# untitled.net
KiCad netlist of a schematic drawn in EAGLE
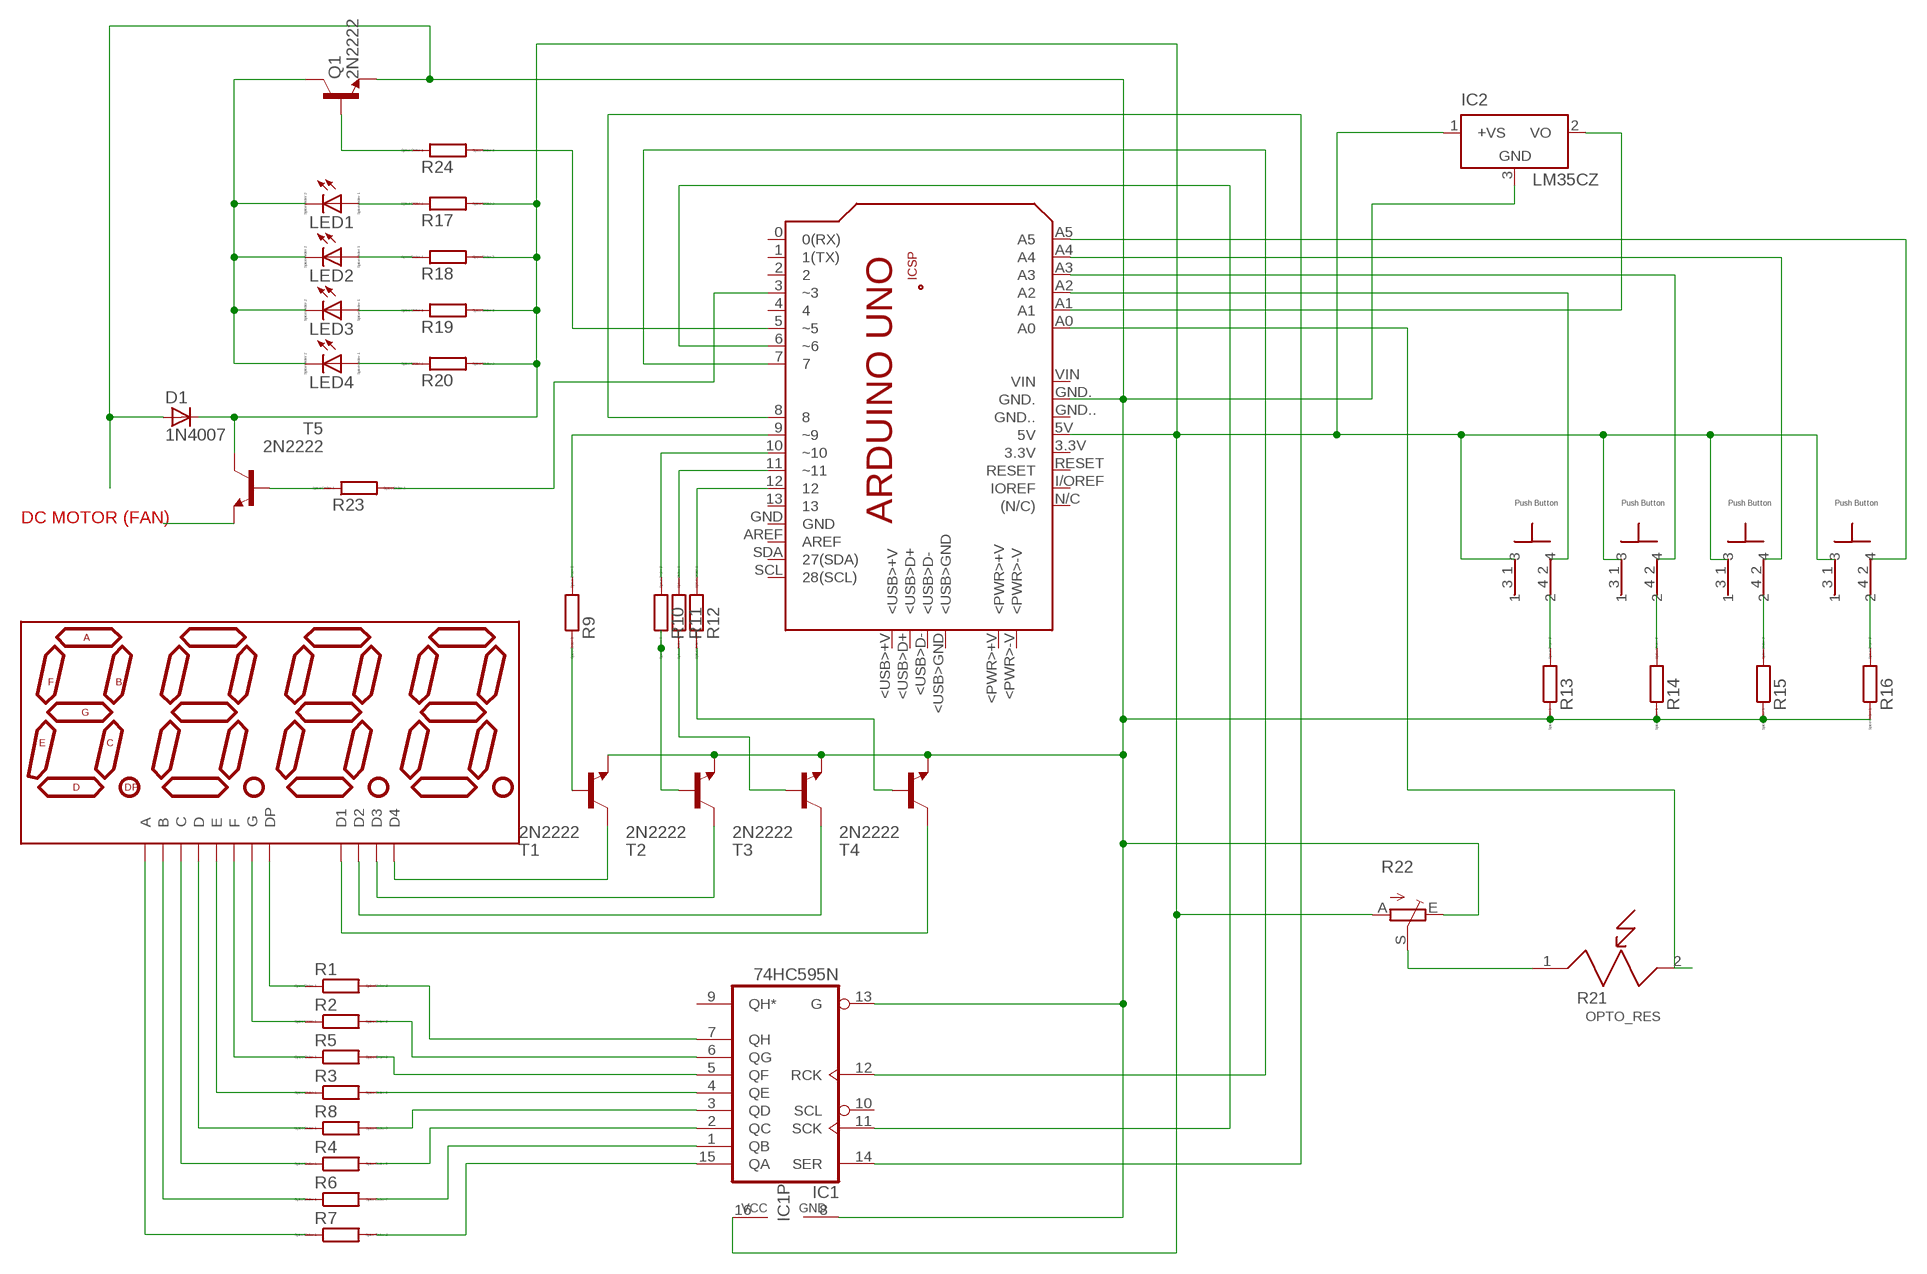
[diagram p0: schematic, sheet 1]

(export (version "E")
  (design (tool "Eeschema 10.0.6"))
  (components
    (comp (ref "D1")
      (value "1N4007")
      (footprint "eagle-import:SMA")
      (libsource (lib "eagle-import") (part "1N4007"))
    )
    (comp (ref "DISP1")
      (value "7-SEGMENT-4DIGIT-COUNTERPTH")
      (footprint "eagle-import:7-SEGMENT-4DIGIT-COUNTER")
      (libsource (lib "eagle-import") (part "7-SEGMENT-4DIGIT-COUNTERPTH"))
    )
    (comp (ref "IC1")
      (value "74HC595N")
      (footprint "eagle-import:DIL16")
      (libsource (lib "eagle-import") (part "74595NHC"))
    )
    (comp (ref "IC2")
      (value "LM35CZ")
      (footprint "eagle-import:TO92")
      (libsource (lib "eagle-import") (part "LM35CZ"))
    )
    (comp (ref "LED1")
      (value "LED_ELD260")
      (footprint "eagle-import:LED_LD260")
      (libsource (lib "eagle-import") (part "LED_ELD260"))
    )
    (comp (ref "LED2")
      (value "LED_ELD260")
      (footprint "eagle-import:LED_LD260")
      (libsource (lib "eagle-import") (part "LED_ELD260"))
    )
    (comp (ref "LED3")
      (value "LED_ELD260")
      (footprint "eagle-import:LED_LD260")
      (libsource (lib "eagle-import") (part "LED_ELD260"))
    )
    (comp (ref "LED4")
      (value "LED_ELD260")
      (footprint "eagle-import:LED_LD260")
      (libsource (lib "eagle-import") (part "LED_ELD260"))
    )
    (comp (ref "PCB1")
      (value "ARDUINO_UNO")
      (footprint "eagle-import:ARDUINO_UNO")
      (libsource (lib "eagle-import") (part "ARDUINO_UNO"))
    )
    (comp (ref "Q1")
      (value "2N2222")
      (footprint "eagle-import:TO18")
      (libsource (lib "eagle-import") (part "2N2222"))
    )
    (comp (ref "R1")
      (value "R0207/10")
      (footprint "eagle-import:0207_10")
      (libsource (lib "eagle-import") (part "R0207/10"))
    )
    (comp (ref "R2")
      (value "R0207/10")
      (footprint "eagle-import:0207_10")
      (libsource (lib "eagle-import") (part "R0207/10"))
    )
    (comp (ref "R3")
      (value "R0207/10")
      (footprint "eagle-import:0207_10")
      (libsource (lib "eagle-import") (part "R0207/10"))
    )
    (comp (ref "R4")
      (value "R0207/10")
      (footprint "eagle-import:0207_10")
      (libsource (lib "eagle-import") (part "R0207/10"))
    )
    (comp (ref "R5")
      (value "R0207/10")
      (footprint "eagle-import:0207_10")
      (libsource (lib "eagle-import") (part "R0207/10"))
    )
    (comp (ref "R6")
      (value "R0207/10")
      (footprint "eagle-import:0207_10")
      (libsource (lib "eagle-import") (part "R0207/10"))
    )
    (comp (ref "R7")
      (value "R0207/10")
      (footprint "eagle-import:0207_10")
      (libsource (lib "eagle-import") (part "R0207/10"))
    )
    (comp (ref "R8")
      (value "R0207/10")
      (footprint "eagle-import:0207_10")
      (libsource (lib "eagle-import") (part "R0207/10"))
    )
    (comp (ref "R9")
      (value "R0207/10")
      (footprint "eagle-import:0207_10")
      (libsource (lib "eagle-import") (part "R0207/10"))
    )
    (comp (ref "R10")
      (value "R0207/10")
      (footprint "eagle-import:0207_10")
      (libsource (lib "eagle-import") (part "R0207/10"))
    )
    (comp (ref "R11")
      (value "R0207/10")
      (footprint "eagle-import:0207_10")
      (libsource (lib "eagle-import") (part "R0207/10"))
    )
    (comp (ref "R12")
      (value "R0207/10")
      (footprint "eagle-import:0207_10")
      (libsource (lib "eagle-import") (part "R0207/10"))
    )
    (comp (ref "R13")
      (value "R0207/10")
      (footprint "eagle-import:0207_10")
      (libsource (lib "eagle-import") (part "R0207/10"))
    )
    (comp (ref "R14")
      (value "R0207/10")
      (footprint "eagle-import:0207_10")
      (libsource (lib "eagle-import") (part "R0207/10"))
    )
    (comp (ref "R15")
      (value "R0207/10")
      (footprint "eagle-import:0207_10")
      (libsource (lib "eagle-import") (part "R0207/10"))
    )
    (comp (ref "R16")
      (value "R0207/10")
      (footprint "eagle-import:0207_10")
      (libsource (lib "eagle-import") (part "R0207/10"))
    )
    (comp (ref "R17")
      (value "R0207/10")
      (footprint "eagle-import:0207_10")
      (libsource (lib "eagle-import") (part "R0207/10"))
    )
    (comp (ref "R18")
      (value "R0207/10")
      (footprint "eagle-import:0207_10")
      (libsource (lib "eagle-import") (part "R0207/10"))
    )
    (comp (ref "R19")
      (value "R0207/10")
      (footprint "eagle-import:0207_10")
      (libsource (lib "eagle-import") (part "R0207/10"))
    )
    (comp (ref "R20")
      (value "R0207/10")
      (footprint "eagle-import:0207_10")
      (libsource (lib "eagle-import") (part "R0207/10"))
    )
    (comp (ref "R21")
      (value "OPTO_RES")
      (footprint "eagle-import:OPTO_RES")
      (libsource (lib "eagle-import") (part "OPTO_RES"))
    )
    (comp (ref "R22")
      (value "TRIM_EU-LI10")
      (footprint "eagle-import:LI10")
      (libsource (lib "eagle-import") (part "TRIM_EU-LI10"))
    )
    (comp (ref "R23")
      (value "R0207/10")
      (footprint "eagle-import:0207_10")
      (libsource (lib "eagle-import") (part "R0207/10"))
    )
    (comp (ref "R24")
      (value "R0207/10")
      (footprint "eagle-import:0207_10")
      (libsource (lib "eagle-import") (part "R0207/10"))
    )
    (comp (ref "T1")
      (value "2N2222")
      (footprint "eagle-import:TO18")
      (libsource (lib "eagle-import") (part "transistor_2N2222"))
    )
    (comp (ref "T2")
      (value "2N2222")
      (footprint "eagle-import:TO18")
      (libsource (lib "eagle-import") (part "transistor_2N2222"))
    )
    (comp (ref "T3")
      (value "2N2222")
      (footprint "eagle-import:TO18")
      (libsource (lib "eagle-import") (part "transistor_2N2222"))
    )
    (comp (ref "T4")
      (value "2N2222")
      (footprint "eagle-import:TO18")
      (libsource (lib "eagle-import") (part "transistor_2N2222"))
    )
    (comp (ref "T5")
      (value "2N2222")
      (footprint "eagle-import:TO18")
      (libsource (lib "eagle-import") (part "transistor_2N2222"))
    )
    (comp (ref "U$1")
      (value "PUSHBTN")
      (footprint "eagle-import:PUSHBTN")
      (libsource (lib "eagle-import") (part "PUSHBTN"))
    )
    (comp (ref "U$2")
      (value "PUSHBTN")
      (footprint "eagle-import:PUSHBTN")
      (libsource (lib "eagle-import") (part "PUSHBTN"))
    )
    (comp (ref "U$3")
      (value "PUSHBTN")
      (footprint "eagle-import:PUSHBTN")
      (libsource (lib "eagle-import") (part "PUSHBTN"))
    )
    (comp (ref "U$4")
      (value "PUSHBTN")
      (footprint "eagle-import:PUSHBTN")
      (libsource (lib "eagle-import") (part "PUSHBTN"))
    )
  )
  (nets
    (net (code "1") (name "Net-(D1-C)") (class "Default")
      (node (ref "D1") (pin "K") (pinfunction "C_K") (pintype "passive"))
      (node (ref "IC1") (pin "16") (pinfunction "VCC_16") (pintype "power_in"))
      (node (ref "IC2") (pin "1") (pinfunction "+VS_1") (pintype "input"))
      (node (ref "PCB1") (pin "5V") (pinfunction "5V_5V") (pintype "bidirectional"))
      (node (ref "R17") (pin "2") (pinfunction "2_2") (pintype "passive"))
      (node (ref "R18") (pin "2") (pinfunction "2_2") (pintype "passive"))
      (node (ref "R19") (pin "2") (pinfunction "2_2") (pintype "passive"))
      (node (ref "R20") (pin "2") (pinfunction "2_2") (pintype "passive"))
      (node (ref "R22") (pin "A") (pinfunction "A_A") (pintype "passive"))
      (node (ref "T5") (pin "3") (pinfunction "C_3") (pintype "passive"))
      (node (ref "U$1") (pin "1") (pinfunction "1_1") (pintype "bidirectional"))
      (node (ref "U$2") (pin "1") (pinfunction "1_1") (pintype "bidirectional"))
      (node (ref "U$3") (pin "1") (pinfunction "1_1") (pintype "bidirectional"))
      (node (ref "U$4") (pin "1") (pinfunction "1_1") (pintype "bidirectional"))
    )
    (net (code "2") (name "Net-(DISP1-A)") (class "Default")
      (node (ref "DISP1") (pin "11") (pinfunction "A_11") (pintype "bidirectional"))
      (node (ref "R7") (pin "1") (pinfunction "1_1") (pintype "passive"))
    )
    (net (code "3") (name "Net-(DISP1-B)") (class "Default")
      (node (ref "DISP1") (pin "7") (pinfunction "B_7") (pintype "bidirectional"))
      (node (ref "R6") (pin "1") (pinfunction "1_1") (pintype "passive"))
    )
    (net (code "4") (name "Net-(DISP1-C)") (class "Default")
      (node (ref "DISP1") (pin "4") (pinfunction "C_4") (pintype "bidirectional"))
      (node (ref "R4") (pin "1") (pinfunction "1_1") (pintype "passive"))
    )
    (net (code "5") (name "Net-(DISP1-D)") (class "Default")
      (node (ref "DISP1") (pin "2") (pinfunction "D_2") (pintype "bidirectional"))
      (node (ref "R8") (pin "1") (pinfunction "1_1") (pintype "passive"))
    )
    (net (code "6") (name "Net-(DISP1-D1)") (class "Default")
      (node (ref "DISP1") (pin "12") (pinfunction "D1_12") (pintype "bidirectional"))
      (node (ref "T4") (pin "3") (pinfunction "C_3") (pintype "passive"))
    )
    (net (code "7") (name "Net-(DISP1-D2)") (class "Default")
      (node (ref "DISP1") (pin "9") (pinfunction "D2_9") (pintype "bidirectional"))
      (node (ref "T3") (pin "3") (pinfunction "C_3") (pintype "passive"))
    )
    (net (code "8") (name "Net-(DISP1-D3)") (class "Default")
      (node (ref "DISP1") (pin "8") (pinfunction "D3_8") (pintype "bidirectional"))
      (node (ref "T2") (pin "3") (pinfunction "C_3") (pintype "passive"))
    )
    (net (code "9") (name "Net-(DISP1-D4)") (class "Default")
      (node (ref "DISP1") (pin "6") (pinfunction "D4_6") (pintype "bidirectional"))
      (node (ref "T1") (pin "3") (pinfunction "C_3") (pintype "passive"))
    )
    (net (code "10") (name "Net-(DISP1-DP)") (class "Default")
      (node (ref "DISP1") (pin "3") (pinfunction "DP_3") (pintype "bidirectional"))
      (node (ref "R1") (pin "1") (pinfunction "1_1") (pintype "passive"))
    )
    (net (code "11") (name "Net-(DISP1-E)") (class "Default")
      (node (ref "DISP1") (pin "1") (pinfunction "E_1") (pintype "bidirectional"))
      (node (ref "R3") (pin "1") (pinfunction "1_1") (pintype "passive"))
    )
    (net (code "12") (name "Net-(DISP1-F)") (class "Default")
      (node (ref "DISP1") (pin "10") (pinfunction "F_10") (pintype "bidirectional"))
      (node (ref "R5") (pin "1") (pinfunction "1_1") (pintype "passive"))
    )
    (net (code "13") (name "Net-(DISP1-G)") (class "Default")
      (node (ref "DISP1") (pin "5") (pinfunction "G_5") (pintype "bidirectional"))
      (node (ref "R2") (pin "1") (pinfunction "1_1") (pintype "passive"))
    )
    (net (code "14") (name "Net-(IC1A-G)") (class "Default")
      (node (ref "D1") (pin "A") (pinfunction "A_A") (pintype "passive"))
      (node (ref "IC1") (pin "13") (pinfunction "G_13") (pintype "input"))
      (node (ref "IC1") (pin "8") (pinfunction "GND_8") (pintype "power_in"))
      (node (ref "IC2") (pin "3") (pinfunction "GND_3") (pintype "power_in"))
      (node (ref "PCB1") (pin "GND.") (pinfunction "GND._GND.") (pintype "bidirectional"))
      (node (ref "Q1") (pin "1") (pinfunction "E_1") (pintype "passive"))
      (node (ref "R13") (pin "1") (pinfunction "1_1") (pintype "passive"))
      (node (ref "R14") (pin "1") (pinfunction "1_1") (pintype "passive"))
      (node (ref "R15") (pin "1") (pinfunction "1_1") (pintype "passive"))
      (node (ref "R16") (pin "1") (pinfunction "1_1") (pintype "passive"))
      (node (ref "R22") (pin "E") (pinfunction "E_E") (pintype "passive"))
      (node (ref "T1") (pin "1") (pinfunction "E_1") (pintype "passive"))
      (node (ref "T2") (pin "1") (pinfunction "E_1") (pintype "passive"))
      (node (ref "T3") (pin "1") (pinfunction "E_1") (pintype "passive"))
      (node (ref "T4") (pin "1") (pinfunction "E_1") (pintype "passive"))
    )
    (net (code "15") (name "Net-(IC1A-QA)") (class "Default")
      (node (ref "IC1") (pin "15") (pinfunction "QA_15") (pintype "tri_state"))
      (node (ref "R7") (pin "2") (pinfunction "2_2") (pintype "passive"))
    )
    (net (code "16") (name "Net-(IC1A-QB)") (class "Default")
      (node (ref "IC1") (pin "1") (pinfunction "QB_1") (pintype "tri_state"))
      (node (ref "R6") (pin "2") (pinfunction "2_2") (pintype "passive"))
    )
    (net (code "17") (name "Net-(IC1A-QC)") (class "Default")
      (node (ref "IC1") (pin "2") (pinfunction "QC_2") (pintype "tri_state"))
      (node (ref "R4") (pin "2") (pinfunction "2_2") (pintype "passive"))
    )
    (net (code "18") (name "Net-(IC1A-QD)") (class "Default")
      (node (ref "IC1") (pin "3") (pinfunction "QD_3") (pintype "tri_state"))
      (node (ref "R8") (pin "2") (pinfunction "2_2") (pintype "passive"))
    )
    (net (code "19") (name "Net-(IC1A-QE)") (class "Default")
      (node (ref "IC1") (pin "4") (pinfunction "QE_4") (pintype "tri_state"))
      (node (ref "R3") (pin "2") (pinfunction "2_2") (pintype "passive"))
    )
    (net (code "20") (name "Net-(IC1A-QF)") (class "Default")
      (node (ref "IC1") (pin "5") (pinfunction "QF_5") (pintype "tri_state"))
      (node (ref "R5") (pin "2") (pinfunction "2_2") (pintype "passive"))
    )
    (net (code "21") (name "Net-(IC1A-QG)") (class "Default")
      (node (ref "IC1") (pin "6") (pinfunction "QG_6") (pintype "tri_state"))
      (node (ref "R2") (pin "2") (pinfunction "2_2") (pintype "passive"))
    )
    (net (code "22") (name "Net-(IC1A-QH)") (class "Default")
      (node (ref "IC1") (pin "7") (pinfunction "QH_7") (pintype "tri_state"))
      (node (ref "R1") (pin "2") (pinfunction "2_2") (pintype "passive"))
    )
    (net (code "23") (name "Net-(IC1A-RCK)") (class "Default")
      (node (ref "IC1") (pin "12") (pinfunction "RCK_12") (pintype "input"))
      (node (ref "PCB1") (pin "7") (pinfunction "7_7") (pintype "bidirectional"))
    )
    (net (code "24") (name "Net-(IC1A-SCK)") (class "Default")
      (node (ref "IC1") (pin "11") (pinfunction "SCK_11") (pintype "input"))
      (node (ref "PCB1") (pin "6") (pinfunction "~{6}_6") (pintype "bidirectional"))
    )
    (net (code "25") (name "Net-(IC1A-SER)") (class "Default")
      (node (ref "IC1") (pin "14") (pinfunction "SER_14") (pintype "input"))
      (node (ref "PCB1") (pin "8") (pinfunction "8_8") (pintype "bidirectional"))
    )
    (net (code "26") (name "Net-(IC2-VO)") (class "Default")
      (node (ref "IC2") (pin "2") (pinfunction "VO_2") (pintype "input"))
      (node (ref "PCB1") (pin "A1") (pinfunction "A1_A1") (pintype "bidirectional"))
    )
    (net (code "27") (name "Net-(LED1-C)") (class "Default")
      (node (ref "LED1") (pin "K") (pinfunction "C_K") (pintype "passive"))
      (node (ref "LED2") (pin "K") (pinfunction "C_K") (pintype "passive"))
      (node (ref "LED3") (pin "K") (pinfunction "C_K") (pintype "passive"))
      (node (ref "LED4") (pin "K") (pinfunction "C_K") (pintype "passive"))
      (node (ref "Q1") (pin "3") (pinfunction "C_3") (pintype "passive"))
    )
    (net (code "28") (name "Net-(LED1-PadA)") (class "Default")
      (node (ref "LED1") (pin "A") (pinfunction "A_A") (pintype "passive"))
      (node (ref "R17") (pin "1") (pinfunction "1_1") (pintype "passive"))
    )
    (net (code "29") (name "Net-(LED2-PadA)") (class "Default")
      (node (ref "LED2") (pin "A") (pinfunction "A_A") (pintype "passive"))
      (node (ref "R18") (pin "1") (pinfunction "1_1") (pintype "passive"))
    )
    (net (code "30") (name "Net-(LED3-PadA)") (class "Default")
      (node (ref "LED3") (pin "A") (pinfunction "A_A") (pintype "passive"))
      (node (ref "R19") (pin "1") (pinfunction "1_1") (pintype "passive"))
    )
    (net (code "31") (name "Net-(LED4-PadA)") (class "Default")
      (node (ref "LED4") (pin "A") (pinfunction "A_A") (pintype "passive"))
      (node (ref "R20") (pin "1") (pinfunction "1_1") (pintype "passive"))
    )
    (net (code "32") (name "Net-(PCB1-Pad12)") (class "Default")
      (node (ref "PCB1") (pin "12") (pinfunction "12_12") (pintype "bidirectional"))
      (node (ref "R12") (pin "2") (pinfunction "2_2") (pintype "passive"))
    )
    (net (code "33") (name "Net-(PCB1-PadA2)") (class "Default")
      (node (ref "PCB1") (pin "A2") (pinfunction "A2_A2") (pintype "bidirectional"))
      (node (ref "U$1") (pin "2") (pinfunction "2_2") (pintype "bidirectional"))
    )
    (net (code "34") (name "Net-(PCB1-PadA3)") (class "Default")
      (node (ref "PCB1") (pin "A3") (pinfunction "A3_A3") (pintype "bidirectional"))
      (node (ref "U$2") (pin "2") (pinfunction "2_2") (pintype "bidirectional"))
    )
    (net (code "35") (name "Net-(PCB1-PadA4)") (class "Default")
      (node (ref "PCB1") (pin "A4") (pinfunction "A4_A4") (pintype "bidirectional"))
      (node (ref "U$3") (pin "2") (pinfunction "2_2") (pintype "bidirectional"))
    )
    (net (code "36") (name "Net-(PCB1-PadA5)") (class "Default")
      (node (ref "PCB1") (pin "A5") (pinfunction "A5_A5") (pintype "bidirectional"))
      (node (ref "U$4") (pin "2") (pinfunction "2_2") (pintype "bidirectional"))
    )
    (net (code "37") (name "Net-(PCB1-~{3})") (class "Default")
      (node (ref "PCB1") (pin "3") (pinfunction "~{3}_3") (pintype "bidirectional"))
      (node (ref "R23") (pin "2") (pinfunction "2_2") (pintype "passive"))
    )
    (net (code "38") (name "Net-(PCB1-~{5})") (class "Default")
      (node (ref "PCB1") (pin "5") (pinfunction "~{5}_5") (pintype "bidirectional"))
      (node (ref "R24") (pin "2") (pinfunction "2_2") (pintype "passive"))
    )
    (net (code "39") (name "Net-(PCB1-~{9})") (class "Default")
      (node (ref "PCB1") (pin "9") (pinfunction "~{9}_9") (pintype "bidirectional"))
      (node (ref "R9") (pin "2") (pinfunction "2_2") (pintype "passive"))
    )
    (net (code "40") (name "Net-(PCB1-~{10})") (class "Default")
      (node (ref "PCB1") (pin "10") (pinfunction "~{10}_10") (pintype "bidirectional"))
      (node (ref "R10") (pin "2") (pinfunction "2_2") (pintype "passive"))
    )
    (net (code "41") (name "Net-(PCB1-~{11})") (class "Default")
      (node (ref "PCB1") (pin "11") (pinfunction "~{11}_11") (pintype "bidirectional"))
      (node (ref "R11") (pin "2") (pinfunction "2_2") (pintype "passive"))
    )
    (net (code "42") (name "Net-(Q1-B)") (class "Default")
      (node (ref "Q1") (pin "2") (pinfunction "B_2") (pintype "passive"))
      (node (ref "R24") (pin "1") (pinfunction "1_1") (pintype "passive"))
    )
    (net (code "43") (name "Net-(R13-Pad2)") (class "Default")
      (node (ref "R13") (pin "2") (pinfunction "2_2") (pintype "passive"))
      (node (ref "U$1") (pin "4") (pinfunction "4_4") (pintype "bidirectional"))
    )
    (net (code "44") (name "Net-(R14-Pad2)") (class "Default")
      (node (ref "R14") (pin "2") (pinfunction "2_2") (pintype "passive"))
      (node (ref "U$2") (pin "4") (pinfunction "4_4") (pintype "bidirectional"))
    )
    (net (code "45") (name "Net-(R15-Pad2)") (class "Default")
      (node (ref "R15") (pin "2") (pinfunction "2_2") (pintype "passive"))
      (node (ref "U$3") (pin "4") (pinfunction "4_4") (pintype "bidirectional"))
    )
    (net (code "46") (name "Net-(R16-Pad2)") (class "Default")
      (node (ref "R16") (pin "2") (pinfunction "2_2") (pintype "passive"))
      (node (ref "U$4") (pin "4") (pinfunction "4_4") (pintype "bidirectional"))
    )
    (net (code "47") (name "Net-(R21-P1)") (class "Default")
      (node (ref "R21") (pin "1") (pinfunction "P1_1") (pintype "bidirectional"))
      (node (ref "R22") (pin "S") (pinfunction "S_S") (pintype "passive"))
    )
    (net (code "48") (name "Net-(R21-P2)") (class "Default")
      (node (ref "PCB1") (pin "A0") (pinfunction "A0_A0") (pintype "bidirectional"))
      (node (ref "R21") (pin "2") (pinfunction "P2_2") (pintype "bidirectional"))
    )
    (net (code "49") (name "Net-(T1-B)") (class "Default")
      (node (ref "R9") (pin "1") (pinfunction "1_1") (pintype "passive"))
      (node (ref "T1") (pin "2") (pinfunction "B_2") (pintype "passive"))
    )
    (net (code "50") (name "Net-(T2-B)") (class "Default")
      (node (ref "R10") (pin "1") (pinfunction "1_1") (pintype "passive"))
      (node (ref "T2") (pin "2") (pinfunction "B_2") (pintype "passive"))
    )
    (net (code "51") (name "Net-(T3-B)") (class "Default")
      (node (ref "R11") (pin "1") (pinfunction "1_1") (pintype "passive"))
      (node (ref "T3") (pin "2") (pinfunction "B_2") (pintype "passive"))
    )
    (net (code "52") (name "Net-(T4-B)") (class "Default")
      (node (ref "R12") (pin "1") (pinfunction "1_1") (pintype "passive"))
      (node (ref "T4") (pin "2") (pinfunction "B_2") (pintype "passive"))
    )
    (net (code "53") (name "Net-(T5-B)") (class "Default")
      (node (ref "R23") (pin "1") (pinfunction "1_1") (pintype "passive"))
      (node (ref "T5") (pin "2") (pinfunction "B_2") (pintype "passive"))
    )
    (net (code "54") (name "unconnected-(IC1A-QH*-Pad9)") (class "Default")
      (node (ref "IC1") (pin "9") (pinfunction "QH*_9") (pintype "tri_state"))
    )
    (net (code "55") (name "unconnected-(IC1A-SCL-Pad10)") (class "Default")
      (node (ref "IC1") (pin "10") (pinfunction "SCL_10") (pintype "input"))
    )
    (net (code "56") (name "unconnected-(PCB1-(N{slash}C)-PadN{slash}C)") (class "Default")
      (node (ref "PCB1") (pin "N/C") (pinfunction "(N/C)_N/C") (pintype "bidirectional"))
    )
    (net (code "57") (name "unconnected-(PCB1-0(RX)-Pad0)") (class "Default")
      (node (ref "PCB1") (pin "0") (pinfunction "0(RX)_0") (pintype "bidirectional"))
    )
    (net (code "58") (name "unconnected-(PCB1-1(TX)-Pad1)") (class "Default")
      (node (ref "PCB1") (pin "1") (pinfunction "1(TX)_1") (pintype "bidirectional"))
    )
    (net (code "59") (name "unconnected-(PCB1-27(SDA)-PadSDA)") (class "Default")
      (node (ref "PCB1") (pin "SDA") (pinfunction "27(SDA)_SDA") (pintype "bidirectional"))
    )
    (net (code "60") (name "unconnected-(PCB1-28(SCL)-PadSCL)") (class "Default")
      (node (ref "PCB1") (pin "SCL") (pinfunction "28(SCL)_SCL") (pintype "bidirectional"))
    )
    (net (code "61") (name "unconnected-(PCB1-IOREF-PadI{slash}OREF)") (class "Default")
      (node (ref "PCB1") (pin "I/OREF") (pinfunction "IOREF_I/OREF") (pintype "bidirectional"))
    )
    (net (code "62") (name "unconnected-(PCB1-Pad+5V)") (class "Default")
      (node (ref "PCB1") (pin "+5V") (pinfunction "+5V_+5V") (pintype "bidirectional"))
    )
    (net (code "63") (name "unconnected-(PCB1-Pad2)") (class "Default")
      (node (ref "PCB1") (pin "2") (pinfunction "2_2") (pintype "bidirectional"))
    )
    (net (code "64") (name "unconnected-(PCB1-Pad3.3V)") (class "Default")
      (node (ref "PCB1") (pin "3.3V") (pinfunction "3.3V_3.3V") (pintype "bidirectional"))
    )
    (net (code "65") (name "unconnected-(PCB1-Pad4)") (class "Default")
      (node (ref "PCB1") (pin "4") (pinfunction "4_4") (pintype "bidirectional"))
    )
    (net (code "66") (name "unconnected-(PCB1-Pad13)") (class "Default")
      (node (ref "PCB1") (pin "13") (pinfunction "13_13") (pintype "bidirectional"))
    )
    (net (code "67") (name "unconnected-(PCB1-Pad<PWR>+V)") (class "Default")
      (node (ref "PCB1") (pin "<PWR>+V") (pinfunction "<PWR>+V_<PWR>+V") (pintype "bidirectional"))
    )
    (net (code "68") (name "unconnected-(PCB1-Pad<PWR>-V)") (class "Default")
      (node (ref "PCB1") (pin "<PWR>-V") (pinfunction "<PWR>-V_<PWR>-V") (pintype "bidirectional"))
    )
    (net (code "69") (name "unconnected-(PCB1-Pad<USB>+V)") (class "Default")
      (node (ref "PCB1") (pin "<USB>+V") (pinfunction "<USB>+V_<USB>+V") (pintype "bidirectional"))
    )
    (net (code "70") (name "unconnected-(PCB1-Pad<USB>D+)") (class "Default")
      (node (ref "PCB1") (pin "<USB>D+") (pinfunction "<USB>D+_<USB>D+") (pintype "bidirectional"))
    )
    (net (code "71") (name "unconnected-(PCB1-Pad<USB>D-)") (class "Default")
      (node (ref "PCB1") (pin "<USB>D-") (pinfunction "<USB>D-_<USB>D-") (pintype "bidirectional"))
    )
    (net (code "72") (name "unconnected-(PCB1-Pad<USB>GND)") (class "Default")
      (node (ref "PCB1") (pin "<USB>GND") (pinfunction "<USB>GND_<USB>GND") (pintype "bidirectional"))
    )
    (net (code "73") (name "unconnected-(PCB1-PadAREF)") (class "Default")
      (node (ref "PCB1") (pin "AREF") (pinfunction "AREF_AREF") (pintype "bidirectional"))
    )
    (net (code "74") (name "unconnected-(PCB1-PadGND)") (class "Default")
      (node (ref "PCB1") (pin "GND") (pinfunction "GND_GND") (pintype "bidirectional"))
    )
    (net (code "75") (name "unconnected-(PCB1-PadGND..)") (class "Default")
      (node (ref "PCB1") (pin "GND..") (pinfunction "GND.._GND..") (pintype "bidirectional"))
    )
    (net (code "76") (name "unconnected-(PCB1-PadGND_)") (class "Default")
      (node (ref "PCB1") (pin "GND_") (pinfunction "GND__GND_") (pintype "bidirectional"))
    )
    (net (code "77") (name "unconnected-(PCB1-PadMISO)") (class "Default")
      (node (ref "PCB1") (pin "MISO") (pinfunction "MISO_MISO") (pintype "bidirectional"))
    )
    (net (code "78") (name "unconnected-(PCB1-PadMOSI)") (class "Default")
      (node (ref "PCB1") (pin "MOSI") (pinfunction "MOSI_MOSI") (pintype "bidirectional"))
    )
    (net (code "79") (name "unconnected-(PCB1-PadRESET)") (class "Default")
      (node (ref "PCB1") (pin "RESET") (pinfunction "RESET_RESET") (pintype "bidirectional"))
    )
    (net (code "80") (name "unconnected-(PCB1-PadRESET.)") (class "Default")
      (node (ref "PCB1") (pin "RESET.") (pinfunction "RESET._RESET.") (pintype "bidirectional"))
    )
    (net (code "81") (name "unconnected-(PCB1-PadSCK)") (class "Default")
      (node (ref "PCB1") (pin "SCK") (pinfunction "SCK_SCK") (pintype "bidirectional"))
    )
    (net (code "82") (name "unconnected-(PCB1-PadVIN)") (class "Default")
      (node (ref "PCB1") (pin "VIN") (pinfunction "VIN_VIN") (pintype "bidirectional"))
    )
    (net (code "83") (name "unconnected-(T5-E-Pad1)") (class "Default")
      (node (ref "T5") (pin "1") (pinfunction "E_1") (pintype "passive"))
    )
    (net (code "84") (name "unconnected-(U$1-Pad3)") (class "Default")
      (node (ref "U$1") (pin "3") (pinfunction "3_3") (pintype "bidirectional"))
    )
    (net (code "85") (name "unconnected-(U$2-Pad3)") (class "Default")
      (node (ref "U$2") (pin "3") (pinfunction "3_3") (pintype "bidirectional"))
    )
    (net (code "86") (name "unconnected-(U$3-Pad3)") (class "Default")
      (node (ref "U$3") (pin "3") (pinfunction "3_3") (pintype "bidirectional"))
    )
    (net (code "87") (name "unconnected-(U$4-Pad3)") (class "Default")
      (node (ref "U$4") (pin "3") (pinfunction "3_3") (pintype "bidirectional"))
    )
  )
)
